# rpmmeter.net
KiCad netlist of a schematic drawn in EAGLE
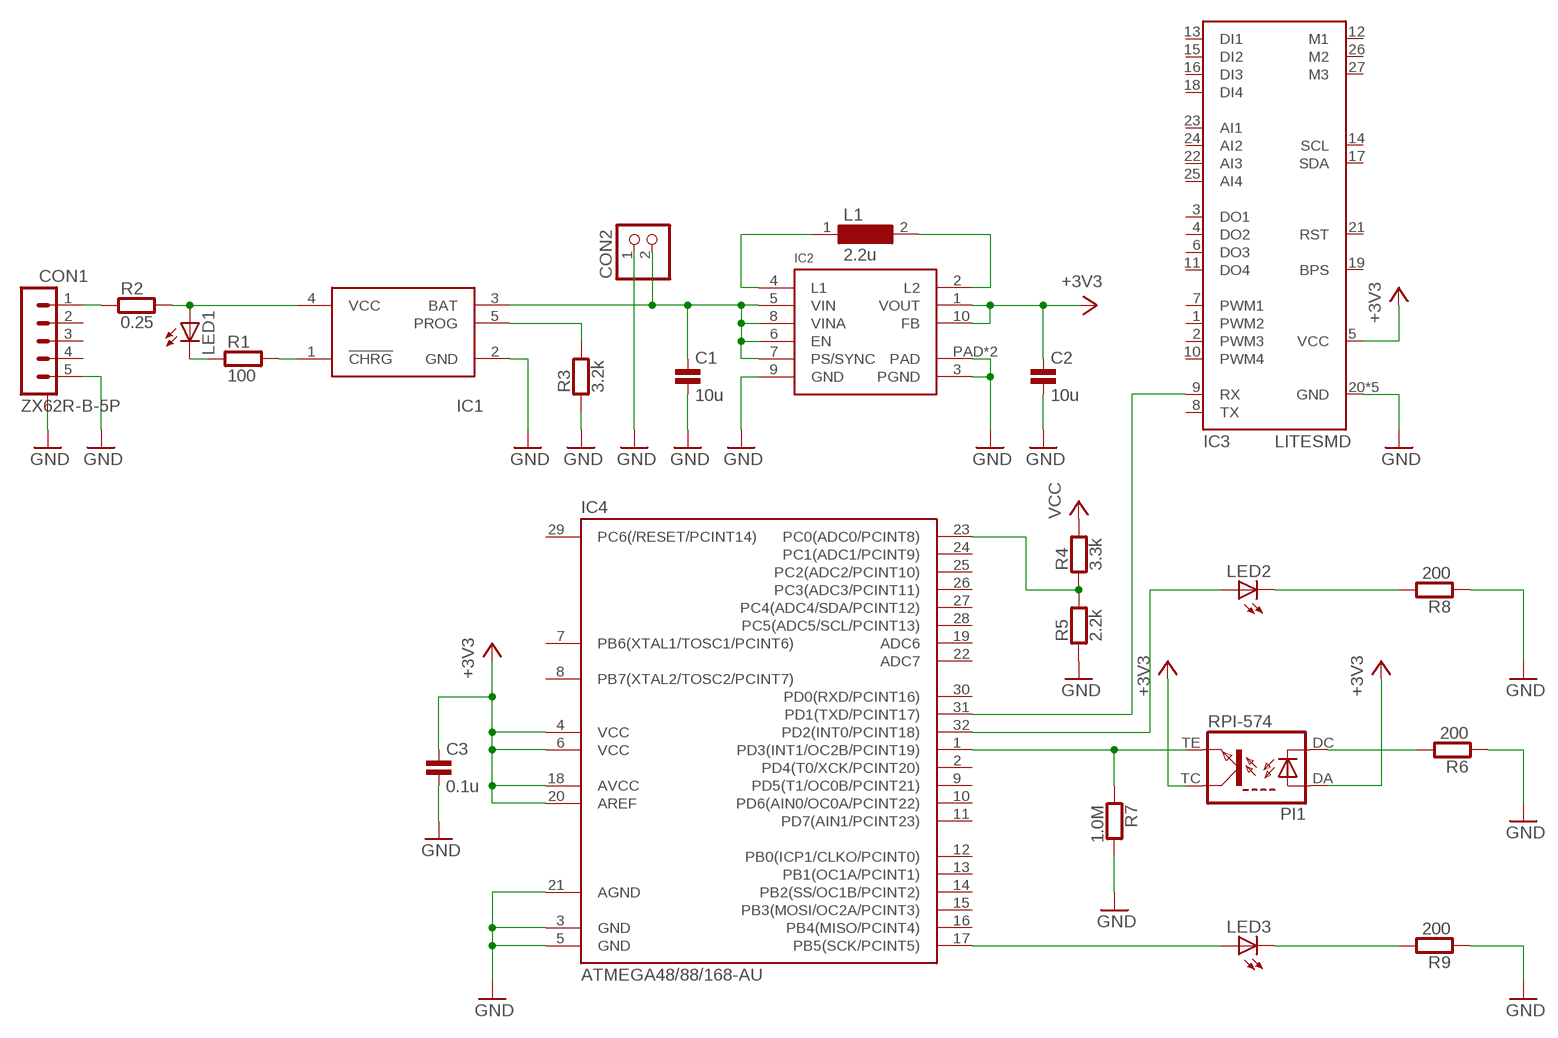
[diagram p0: schematic, sheet 1]

(export (version "E")
  (design (tool "Eeschema 10.0.6"))
  (components
    (comp (ref "C1")
      (value "10u")
      (footprint "eagle-import:0603")
      (libsource (lib "eagle-import") (part "C0603"))
    )
    (comp (ref "C2")
      (value "10u")
      (footprint "eagle-import:0603")
      (libsource (lib "eagle-import") (part "C0603"))
    )
    (comp (ref "C3")
      (value "0.1u")
      (footprint "eagle-import:0603")
      (libsource (lib "eagle-import") (part "C0603"))
    )
    (comp (ref "CON1")
      (value "ZX62R-B-5P")
      (footprint "eagle-import:MICRO-B")
      (libsource (lib "eagle-import") (part "ZX62R-B-5P"))
    )
    (comp (ref "CON2")
      (value "JST-PH2")
      (footprint "eagle-import:JST-PH2")
      (libsource (lib "eagle-import") (part "JST-PH2"))
    )
    (comp (ref "IC1")
      (value "LTC4054")
      (footprint "eagle-import:TSOT23-5")
      (libsource (lib "eagle-import") (part "LTC4054"))
    )
    (comp (ref "IC2")
      (value "TPS6300XDRCT")
      (footprint "eagle-import:S-PVSON-N10")
      (libsource (lib "eagle-import") (part "TPS6300XDRCT"))
    )
    (comp (ref "IC3")
      (value "LITESMD")
      (footprint "eagle-import:LITE")
      (libsource (lib "eagle-import") (part "LITESMD"))
    )
    (comp (ref "IC4")
      (value "ATMEGA48/88/168-AU")
      (footprint "eagle-import:TQFP32-08")
      (libsource (lib "eagle-import") (part "ATMEGA48/88/168-AU"))
    )
    (comp (ref "L1")
      (value "2.2u")
      (footprint "eagle-import:VLF4012ST")
      (libsource (lib "eagle-import") (part "VLF4012ST"))
    )
    (comp (ref "LED1")
      (value "LEDSML0603")
      (footprint "eagle-import:SML0603")
      (libsource (lib "eagle-import") (part "LEDSML0603"))
    )
    (comp (ref "LED2")
      (value "LEDSML0603")
      (footprint "eagle-import:SML0603")
      (libsource (lib "eagle-import") (part "LEDSML0603"))
    )
    (comp (ref "LED3")
      (value "LEDSML0603")
      (footprint "eagle-import:SML0603")
      (libsource (lib "eagle-import") (part "LEDSML0603"))
    )
    (comp (ref "PI1")
      (value "RPI-574")
      (footprint "eagle-import:RPI-574")
      (libsource (lib "eagle-import") (part "RPI-574"))
    )
    (comp (ref "R1")
      (value "100")
      (footprint "eagle-import:0603")
      (libsource (lib "eagle-import") (part "R0603"))
    )
    (comp (ref "R2")
      (value "0.25")
      (footprint "eagle-import:0603")
      (libsource (lib "eagle-import") (part "R0603"))
    )
    (comp (ref "R3")
      (value "3.2k")
      (footprint "eagle-import:0603")
      (libsource (lib "eagle-import") (part "R0603"))
    )
    (comp (ref "R4")
      (value "3.3k")
      (footprint "eagle-import:0603")
      (libsource (lib "eagle-import") (part "R0603"))
    )
    (comp (ref "R5")
      (value "2.2k")
      (footprint "eagle-import:0603")
      (libsource (lib "eagle-import") (part "R0603"))
    )
    (comp (ref "R6")
      (value "200")
      (footprint "eagle-import:0603")
      (libsource (lib "eagle-import") (part "R0603"))
    )
    (comp (ref "R7")
      (value "1.0M")
      (footprint "eagle-import:0603")
      (libsource (lib "eagle-import") (part "R0603"))
    )
    (comp (ref "R8")
      (value "200")
      (footprint "eagle-import:0603")
      (libsource (lib "eagle-import") (part "R0603"))
    )
    (comp (ref "R9")
      (value "200")
      (footprint "eagle-import:0603")
      (libsource (lib "eagle-import") (part "R0603"))
    )
  )
  (nets
    (net (code "1") (name "+3V3") (class "Default")
      (node (ref "C2") (pin "1") (pinfunction "P$1_1") (pintype "passive"))
      (node (ref "C3") (pin "1") (pinfunction "P$1_1") (pintype "passive"))
      (node (ref "IC2") (pin "1") (pinfunction "VOUT_1") (pintype "output"))
      (node (ref "IC2") (pin "10") (pinfunction "FB_10") (pintype "input"))
      (node (ref "IC3") (pin "5") (pinfunction "VCC_5") (pintype "power_in"))
      (node (ref "IC4") (pin "18") (pinfunction "AVCC_18") (pintype "passive"))
      (node (ref "IC4") (pin "20") (pinfunction "AREF_20") (pintype "passive"))
      (node (ref "IC4") (pin "4") (pinfunction "VCC_4") (pintype "power_in"))
      (node (ref "IC4") (pin "6") (pinfunction "VCC_6") (pintype "power_in"))
      (node (ref "PI1") (pin "DA") (pinfunction "DA_DA") (pintype "passive"))
      (node (ref "PI1") (pin "TC") (pinfunction "TC_TC") (pintype "passive"))
    )
    (net (code "2") (name "GND") (class "Default")
      (node (ref "C1") (pin "2") (pinfunction "P$2_2") (pintype "passive"))
      (node (ref "C2") (pin "2") (pinfunction "P$2_2") (pintype "passive"))
      (node (ref "C3") (pin "2") (pinfunction "P$2_2") (pintype "passive"))
      (node (ref "CON1") (pin "5") (pinfunction "1.VBUS_5") (pintype "passive"))
      (node (ref "CON1") (pin "CASE@1") (pinfunction "P$1_CASE@1") (pintype "bidirectional"))
      (node (ref "CON1") (pin "CASE@2") (pinfunction "P$1_CASE@2") (pintype "bidirectional"))
      (node (ref "CON1") (pin "CASE@3") (pinfunction "P$1_CASE@3") (pintype "bidirectional"))
      (node (ref "CON1") (pin "CASE@4") (pinfunction "P$1_CASE@4") (pintype "bidirectional"))
      (node (ref "CON2") (pin "1") (pinfunction "1_1") (pintype "passive"))
      (node (ref "IC1") (pin "2") (pinfunction "GND_2") (pintype "power_in"))
      (node (ref "IC2") (pin "3") (pinfunction "PGND_3") (pintype "power_in"))
      (node (ref "IC2") (pin "9") (pinfunction "GND_9") (pintype "power_in"))
      (node (ref "IC2") (pin "PAD") (pinfunction "PAD_PAD") (pintype "power_in"))
      (node (ref "IC2") (pin "PAD@1") (pinfunction "PAD_PAD@1") (pintype "power_in"))
      (node (ref "IC3") (pin "20") (pinfunction "GND_20") (pintype "power_in"))
      (node (ref "IC3") (pin "28") (pinfunction "GND_28") (pintype "power_in"))
      (node (ref "IC3") (pin "30") (pinfunction "GND_30") (pintype "power_in"))
      (node (ref "IC3") (pin "31") (pinfunction "GND_31") (pintype "power_in"))
      (node (ref "IC3") (pin "32") (pinfunction "GND_32") (pintype "power_in"))
      (node (ref "IC4") (pin "21") (pinfunction "AGND_21") (pintype "power_in"))
      (node (ref "IC4") (pin "3") (pinfunction "GND_3") (pintype "power_in"))
      (node (ref "IC4") (pin "5") (pinfunction "GND_5") (pintype "power_in"))
      (node (ref "R3") (pin "1") (pinfunction "P$1_1") (pintype "passive"))
      (node (ref "R5") (pin "1") (pinfunction "P$1_1") (pintype "passive"))
      (node (ref "R6") (pin "1") (pinfunction "P$1_1") (pintype "passive"))
      (node (ref "R7") (pin "2") (pinfunction "P$2_2") (pintype "passive"))
      (node (ref "R8") (pin "1") (pinfunction "P$1_1") (pintype "passive"))
      (node (ref "R9") (pin "1") (pinfunction "P$1_1") (pintype "passive"))
    )
    (net (code "3") (name "Net-(CON1-5.GND)") (class "Default")
      (node (ref "CON1") (pin "1") (pinfunction "5.GND_1") (pintype "passive"))
      (node (ref "R2") (pin "1") (pinfunction "P$1_1") (pintype "passive"))
    )
    (net (code "4") (name "Net-(IC1-PROG)") (class "Default")
      (node (ref "IC1") (pin "5") (pinfunction "PROG_5") (pintype "passive"))
      (node (ref "R3") (pin "2") (pinfunction "P$2_2") (pintype "passive"))
    )
    (net (code "5") (name "Net-(IC1-VCC)") (class "Default")
      (node (ref "IC1") (pin "4") (pinfunction "VCC_4") (pintype "power_in"))
      (node (ref "LED1") (pin "A") (pinfunction "A_A") (pintype "passive"))
      (node (ref "R2") (pin "2") (pinfunction "P$2_2") (pintype "passive"))
    )
    (net (code "6") (name "Net-(IC1-~{CHRG})") (class "Default")
      (node (ref "IC1") (pin "1") (pinfunction "~{CHRG}_1") (pintype "output"))
      (node (ref "R1") (pin "2") (pinfunction "P$2_2") (pintype "passive"))
    )
    (net (code "7") (name "Net-(IC2-L1)") (class "Default")
      (node (ref "IC2") (pin "4") (pinfunction "L1_4") (pintype "bidirectional"))
      (node (ref "L1") (pin "1") (pinfunction "1_1") (pintype "passive"))
    )
    (net (code "8") (name "Net-(IC2-L2)") (class "Default")
      (node (ref "IC2") (pin "2") (pinfunction "L2_2") (pintype "bidirectional"))
      (node (ref "L1") (pin "2") (pinfunction "2_2") (pintype "passive"))
    )
    (net (code "9") (name "Net-(IC3-RX)") (class "Default")
      (node (ref "IC3") (pin "9") (pinfunction "RX_9") (pintype "input"))
      (node (ref "IC4") (pin "31") (pinfunction "PD1(TXD/PCINT17)_31") (pintype "bidirectional"))
    )
    (net (code "10") (name "Net-(IC4-PB5(SCK{slash}PCINT5))") (class "Default")
      (node (ref "IC4") (pin "17") (pinfunction "PB5(SCK/PCINT5)_17") (pintype "bidirectional"))
      (node (ref "LED3") (pin "A") (pinfunction "A_A") (pintype "passive"))
    )
    (net (code "11") (name "Net-(IC4-PC0(ADC0{slash}PCINT8))") (class "Default")
      (node (ref "IC4") (pin "23") (pinfunction "PC0(ADC0/PCINT8)_23") (pintype "bidirectional"))
      (node (ref "R4") (pin "1") (pinfunction "P$1_1") (pintype "passive"))
      (node (ref "R5") (pin "2") (pinfunction "P$2_2") (pintype "passive"))
    )
    (net (code "12") (name "Net-(IC4-PD2(INT0{slash}PCINT18))") (class "Default")
      (node (ref "IC4") (pin "32") (pinfunction "PD2(INT0/PCINT18)_32") (pintype "bidirectional"))
      (node (ref "LED2") (pin "A") (pinfunction "A_A") (pintype "passive"))
    )
    (net (code "13") (name "Net-(IC4-PD3(INT1{slash}OC2B{slash}PCINT19))") (class "Default")
      (node (ref "IC4") (pin "1") (pinfunction "PD3(INT1/OC2B/PCINT19)_1") (pintype "bidirectional"))
      (node (ref "PI1") (pin "TE") (pinfunction "TE_TE") (pintype "passive"))
      (node (ref "R7") (pin "1") (pinfunction "P$1_1") (pintype "passive"))
    )
    (net (code "14") (name "Net-(R1-P$1)") (class "Default")
      (node (ref "LED1") (pin "C") (pinfunction "C_C") (pintype "passive"))
      (node (ref "R1") (pin "1") (pinfunction "P$1_1") (pintype "passive"))
    )
    (net (code "15") (name "Net-(R6-P$2)") (class "Default")
      (node (ref "PI1") (pin "DC") (pinfunction "DC_DC") (pintype "passive"))
      (node (ref "R6") (pin "2") (pinfunction "P$2_2") (pintype "passive"))
    )
    (net (code "16") (name "Net-(R8-P$2)") (class "Default")
      (node (ref "LED2") (pin "C") (pinfunction "C_C") (pintype "passive"))
      (node (ref "R8") (pin "2") (pinfunction "P$2_2") (pintype "passive"))
    )
    (net (code "17") (name "Net-(R9-P$2)") (class "Default")
      (node (ref "LED3") (pin "C") (pinfunction "C_C") (pintype "passive"))
      (node (ref "R9") (pin "2") (pinfunction "P$2_2") (pintype "passive"))
    )
    (net (code "18") (name "VCC") (class "Default")
      (node (ref "C1") (pin "1") (pinfunction "P$1_1") (pintype "passive"))
      (node (ref "CON2") (pin "2") (pinfunction "2_2") (pintype "passive"))
      (node (ref "IC1") (pin "3") (pinfunction "BAT_3") (pintype "power_in"))
      (node (ref "IC2") (pin "5") (pinfunction "VIN_5") (pintype "power_in"))
      (node (ref "IC2") (pin "6") (pinfunction "EN_6") (pintype "input"))
      (node (ref "IC2") (pin "7") (pinfunction "PS/SYNC_7") (pintype "input"))
      (node (ref "IC2") (pin "8") (pinfunction "VINA_8") (pintype "power_in"))
      (node (ref "R4") (pin "2") (pinfunction "P$2_2") (pintype "passive"))
    )
    (net (code "19") (name "unconnected-(CON1-2.D--Pad4)") (class "Default")
      (node (ref "CON1") (pin "4") (pinfunction "2.D-_4") (pintype "passive"))
    )
    (net (code "20") (name "unconnected-(CON1-3.D+-Pad3)") (class "Default")
      (node (ref "CON1") (pin "3") (pinfunction "3.D+_3") (pintype "passive"))
    )
    (net (code "21") (name "unconnected-(CON1-4.ID-Pad2)") (class "Default")
      (node (ref "CON1") (pin "2") (pinfunction "4.ID_2") (pintype "passive"))
    )
    (net (code "22") (name "unconnected-(IC3-AI1-Pad23)") (class "Default")
      (node (ref "IC3") (pin "23") (pinfunction "AI1_23") (pintype "input"))
    )
    (net (code "23") (name "unconnected-(IC3-AI2-Pad24)") (class "Default")
      (node (ref "IC3") (pin "24") (pinfunction "AI2_24") (pintype "input"))
    )
    (net (code "24") (name "unconnected-(IC3-AI3-Pad22)") (class "Default")
      (node (ref "IC3") (pin "22") (pinfunction "AI3_22") (pintype "input"))
    )
    (net (code "25") (name "unconnected-(IC3-AI4-Pad25)") (class "Default")
      (node (ref "IC3") (pin "25") (pinfunction "AI4_25") (pintype "input"))
    )
    (net (code "26") (name "unconnected-(IC3-BPS-Pad19)") (class "Default")
      (node (ref "IC3") (pin "19") (pinfunction "BPS_19") (pintype "input"))
    )
    (net (code "27") (name "unconnected-(IC3-DI1-Pad13)") (class "Default")
      (node (ref "IC3") (pin "13") (pinfunction "DI1_13") (pintype "input"))
    )
    (net (code "28") (name "unconnected-(IC3-DI2-Pad15)") (class "Default")
      (node (ref "IC3") (pin "15") (pinfunction "DI2_15") (pintype "input"))
    )
    (net (code "29") (name "unconnected-(IC3-DI3-Pad16)") (class "Default")
      (node (ref "IC3") (pin "16") (pinfunction "DI3_16") (pintype "input"))
    )
    (net (code "30") (name "unconnected-(IC3-DI4-Pad18)") (class "Default")
      (node (ref "IC3") (pin "18") (pinfunction "DI4_18") (pintype "input"))
    )
    (net (code "31") (name "unconnected-(IC3-DO1-Pad3)") (class "Default")
      (node (ref "IC3") (pin "3") (pinfunction "DO1_3") (pintype "output"))
    )
    (net (code "32") (name "unconnected-(IC3-DO2-Pad4)") (class "Default")
      (node (ref "IC3") (pin "4") (pinfunction "DO2_4") (pintype "output"))
    )
    (net (code "33") (name "unconnected-(IC3-DO3-Pad6)") (class "Default")
      (node (ref "IC3") (pin "6") (pinfunction "DO3_6") (pintype "output"))
    )
    (net (code "34") (name "unconnected-(IC3-DO4-Pad11)") (class "Default")
      (node (ref "IC3") (pin "11") (pinfunction "DO4_11") (pintype "output"))
    )
    (net (code "35") (name "unconnected-(IC3-M1-Pad12)") (class "Default")
      (node (ref "IC3") (pin "12") (pinfunction "M1_12") (pintype "input"))
    )
    (net (code "36") (name "unconnected-(IC3-M2-Pad26)") (class "Default")
      (node (ref "IC3") (pin "26") (pinfunction "M2_26") (pintype "input"))
    )
    (net (code "37") (name "unconnected-(IC3-M3-Pad27)") (class "Default")
      (node (ref "IC3") (pin "27") (pinfunction "M3_27") (pintype "input"))
    )
    (net (code "38") (name "unconnected-(IC3-PWM1-Pad7)") (class "Default")
      (node (ref "IC3") (pin "7") (pinfunction "PWM1_7") (pintype "output"))
    )
    (net (code "39") (name "unconnected-(IC3-PWM2-Pad1)") (class "Default")
      (node (ref "IC3") (pin "1") (pinfunction "PWM2_1") (pintype "output"))
    )
    (net (code "40") (name "unconnected-(IC3-PWM3-Pad2)") (class "Default")
      (node (ref "IC3") (pin "2") (pinfunction "PWM3_2") (pintype "output"))
    )
    (net (code "41") (name "unconnected-(IC3-PWM4-Pad10)") (class "Default")
      (node (ref "IC3") (pin "10") (pinfunction "PWM4_10") (pintype "output"))
    )
    (net (code "42") (name "unconnected-(IC3-RST-Pad21)") (class "Default")
      (node (ref "IC3") (pin "21") (pinfunction "RST_21") (pintype "input"))
    )
    (net (code "43") (name "unconnected-(IC3-SCL-Pad14)") (class "Default")
      (node (ref "IC3") (pin "14") (pinfunction "SCL_14") (pintype "bidirectional"))
    )
    (net (code "44") (name "unconnected-(IC3-SDA-Pad17)") (class "Default")
      (node (ref "IC3") (pin "17") (pinfunction "SDA_17") (pintype "bidirectional"))
    )
    (net (code "45") (name "unconnected-(IC3-TX-Pad8)") (class "Default")
      (node (ref "IC3") (pin "8") (pinfunction "TX_8") (pintype "output"))
    )
    (net (code "46") (name "unconnected-(IC4-ADC6-Pad19)") (class "Default")
      (node (ref "IC4") (pin "19") (pinfunction "ADC6_19") (pintype "passive"))
    )
    (net (code "47") (name "unconnected-(IC4-ADC7-Pad22)") (class "Default")
      (node (ref "IC4") (pin "22") (pinfunction "ADC7_22") (pintype "passive"))
    )
    (net (code "48") (name "unconnected-(IC4-PB0(ICP1{slash}CLKO{slash}PCINT0)-Pad12)") (class "Default")
      (node (ref "IC4") (pin "12") (pinfunction "PB0(ICP1/CLKO/PCINT0)_12") (pintype "bidirectional"))
    )
    (net (code "49") (name "unconnected-(IC4-PB1(OC1A{slash}PCINT1)-Pad13)") (class "Default")
      (node (ref "IC4") (pin "13") (pinfunction "PB1(OC1A/PCINT1)_13") (pintype "bidirectional"))
    )
    (net (code "50") (name "unconnected-(IC4-PB2(SS{slash}OC1B{slash}PCINT2)-Pad14)") (class "Default")
      (node (ref "IC4") (pin "14") (pinfunction "PB2(SS/OC1B/PCINT2)_14") (pintype "bidirectional"))
    )
    (net (code "51") (name "unconnected-(IC4-PB3(MOSI{slash}OC2A{slash}PCINT3)-Pad15)") (class "Default")
      (node (ref "IC4") (pin "15") (pinfunction "PB3(MOSI/OC2A/PCINT3)_15") (pintype "bidirectional"))
    )
    (net (code "52") (name "unconnected-(IC4-PB4(MISO{slash}PCINT4)-Pad16)") (class "Default")
      (node (ref "IC4") (pin "16") (pinfunction "PB4(MISO/PCINT4)_16") (pintype "bidirectional"))
    )
    (net (code "53") (name "unconnected-(IC4-PB6(XTAL1{slash}TOSC1{slash}PCINT6)-Pad7)") (class "Default")
      (node (ref "IC4") (pin "7") (pinfunction "PB6(XTAL1/TOSC1/PCINT6)_7") (pintype "bidirectional"))
    )
    (net (code "54") (name "unconnected-(IC4-PB7(XTAL2{slash}TOSC2{slash}PCINT7)-Pad8)") (class "Default")
      (node (ref "IC4") (pin "8") (pinfunction "PB7(XTAL2/TOSC2/PCINT7)_8") (pintype "bidirectional"))
    )
    (net (code "55") (name "unconnected-(IC4-PC1(ADC1{slash}PCINT9)-Pad24)") (class "Default")
      (node (ref "IC4") (pin "24") (pinfunction "PC1(ADC1/PCINT9)_24") (pintype "bidirectional"))
    )
    (net (code "56") (name "unconnected-(IC4-PC2(ADC2{slash}PCINT10)-Pad25)") (class "Default")
      (node (ref "IC4") (pin "25") (pinfunction "PC2(ADC2/PCINT10)_25") (pintype "bidirectional"))
    )
    (net (code "57") (name "unconnected-(IC4-PC3(ADC3{slash}PCINT11)-Pad26)") (class "Default")
      (node (ref "IC4") (pin "26") (pinfunction "PC3(ADC3/PCINT11)_26") (pintype "bidirectional"))
    )
    (net (code "58") (name "unconnected-(IC4-PC4(ADC4{slash}SDA{slash}PCINT12)-Pad27)") (class "Default")
      (node (ref "IC4") (pin "27") (pinfunction "PC4(ADC4/SDA/PCINT12)_27") (pintype "bidirectional"))
    )
    (net (code "59") (name "unconnected-(IC4-PC5(ADC5{slash}SCL{slash}PCINT13)-Pad28)") (class "Default")
      (node (ref "IC4") (pin "28") (pinfunction "PC5(ADC5/SCL/PCINT13)_28") (pintype "bidirectional"))
    )
    (net (code "60") (name "unconnected-(IC4-PC6({slash}RESET{slash}PCINT14)-Pad29)") (class "Default")
      (node (ref "IC4") (pin "29") (pinfunction "PC6(/RESET/PCINT14)_29") (pintype "bidirectional"))
    )
    (net (code "61") (name "unconnected-(IC4-PD0(RXD{slash}PCINT16)-Pad30)") (class "Default")
      (node (ref "IC4") (pin "30") (pinfunction "PD0(RXD/PCINT16)_30") (pintype "bidirectional"))
    )
    (net (code "62") (name "unconnected-(IC4-PD4(T0{slash}XCK{slash}PCINT20)-Pad2)") (class "Default")
      (node (ref "IC4") (pin "2") (pinfunction "PD4(T0/XCK/PCINT20)_2") (pintype "bidirectional"))
    )
    (net (code "63") (name "unconnected-(IC4-PD5(T1{slash}OC0B{slash}PCINT21)-Pad9)") (class "Default")
      (node (ref "IC4") (pin "9") (pinfunction "PD5(T1/OC0B/PCINT21)_9") (pintype "bidirectional"))
    )
    (net (code "64") (name "unconnected-(IC4-PD6(AIN0{slash}OC0A{slash}PCINT22)-Pad10)") (class "Default")
      (node (ref "IC4") (pin "10") (pinfunction "PD6(AIN0/OC0A/PCINT22)_10") (pintype "bidirectional"))
    )
    (net (code "65") (name "unconnected-(IC4-PD7(AIN1{slash}PCINT23)-Pad11)") (class "Default")
      (node (ref "IC4") (pin "11") (pinfunction "PD7(AIN1/PCINT23)_11") (pintype "bidirectional"))
    )
  )
)
